# Sheet_1.net
KiCad netlist of a schematic drawn in EasyEDA
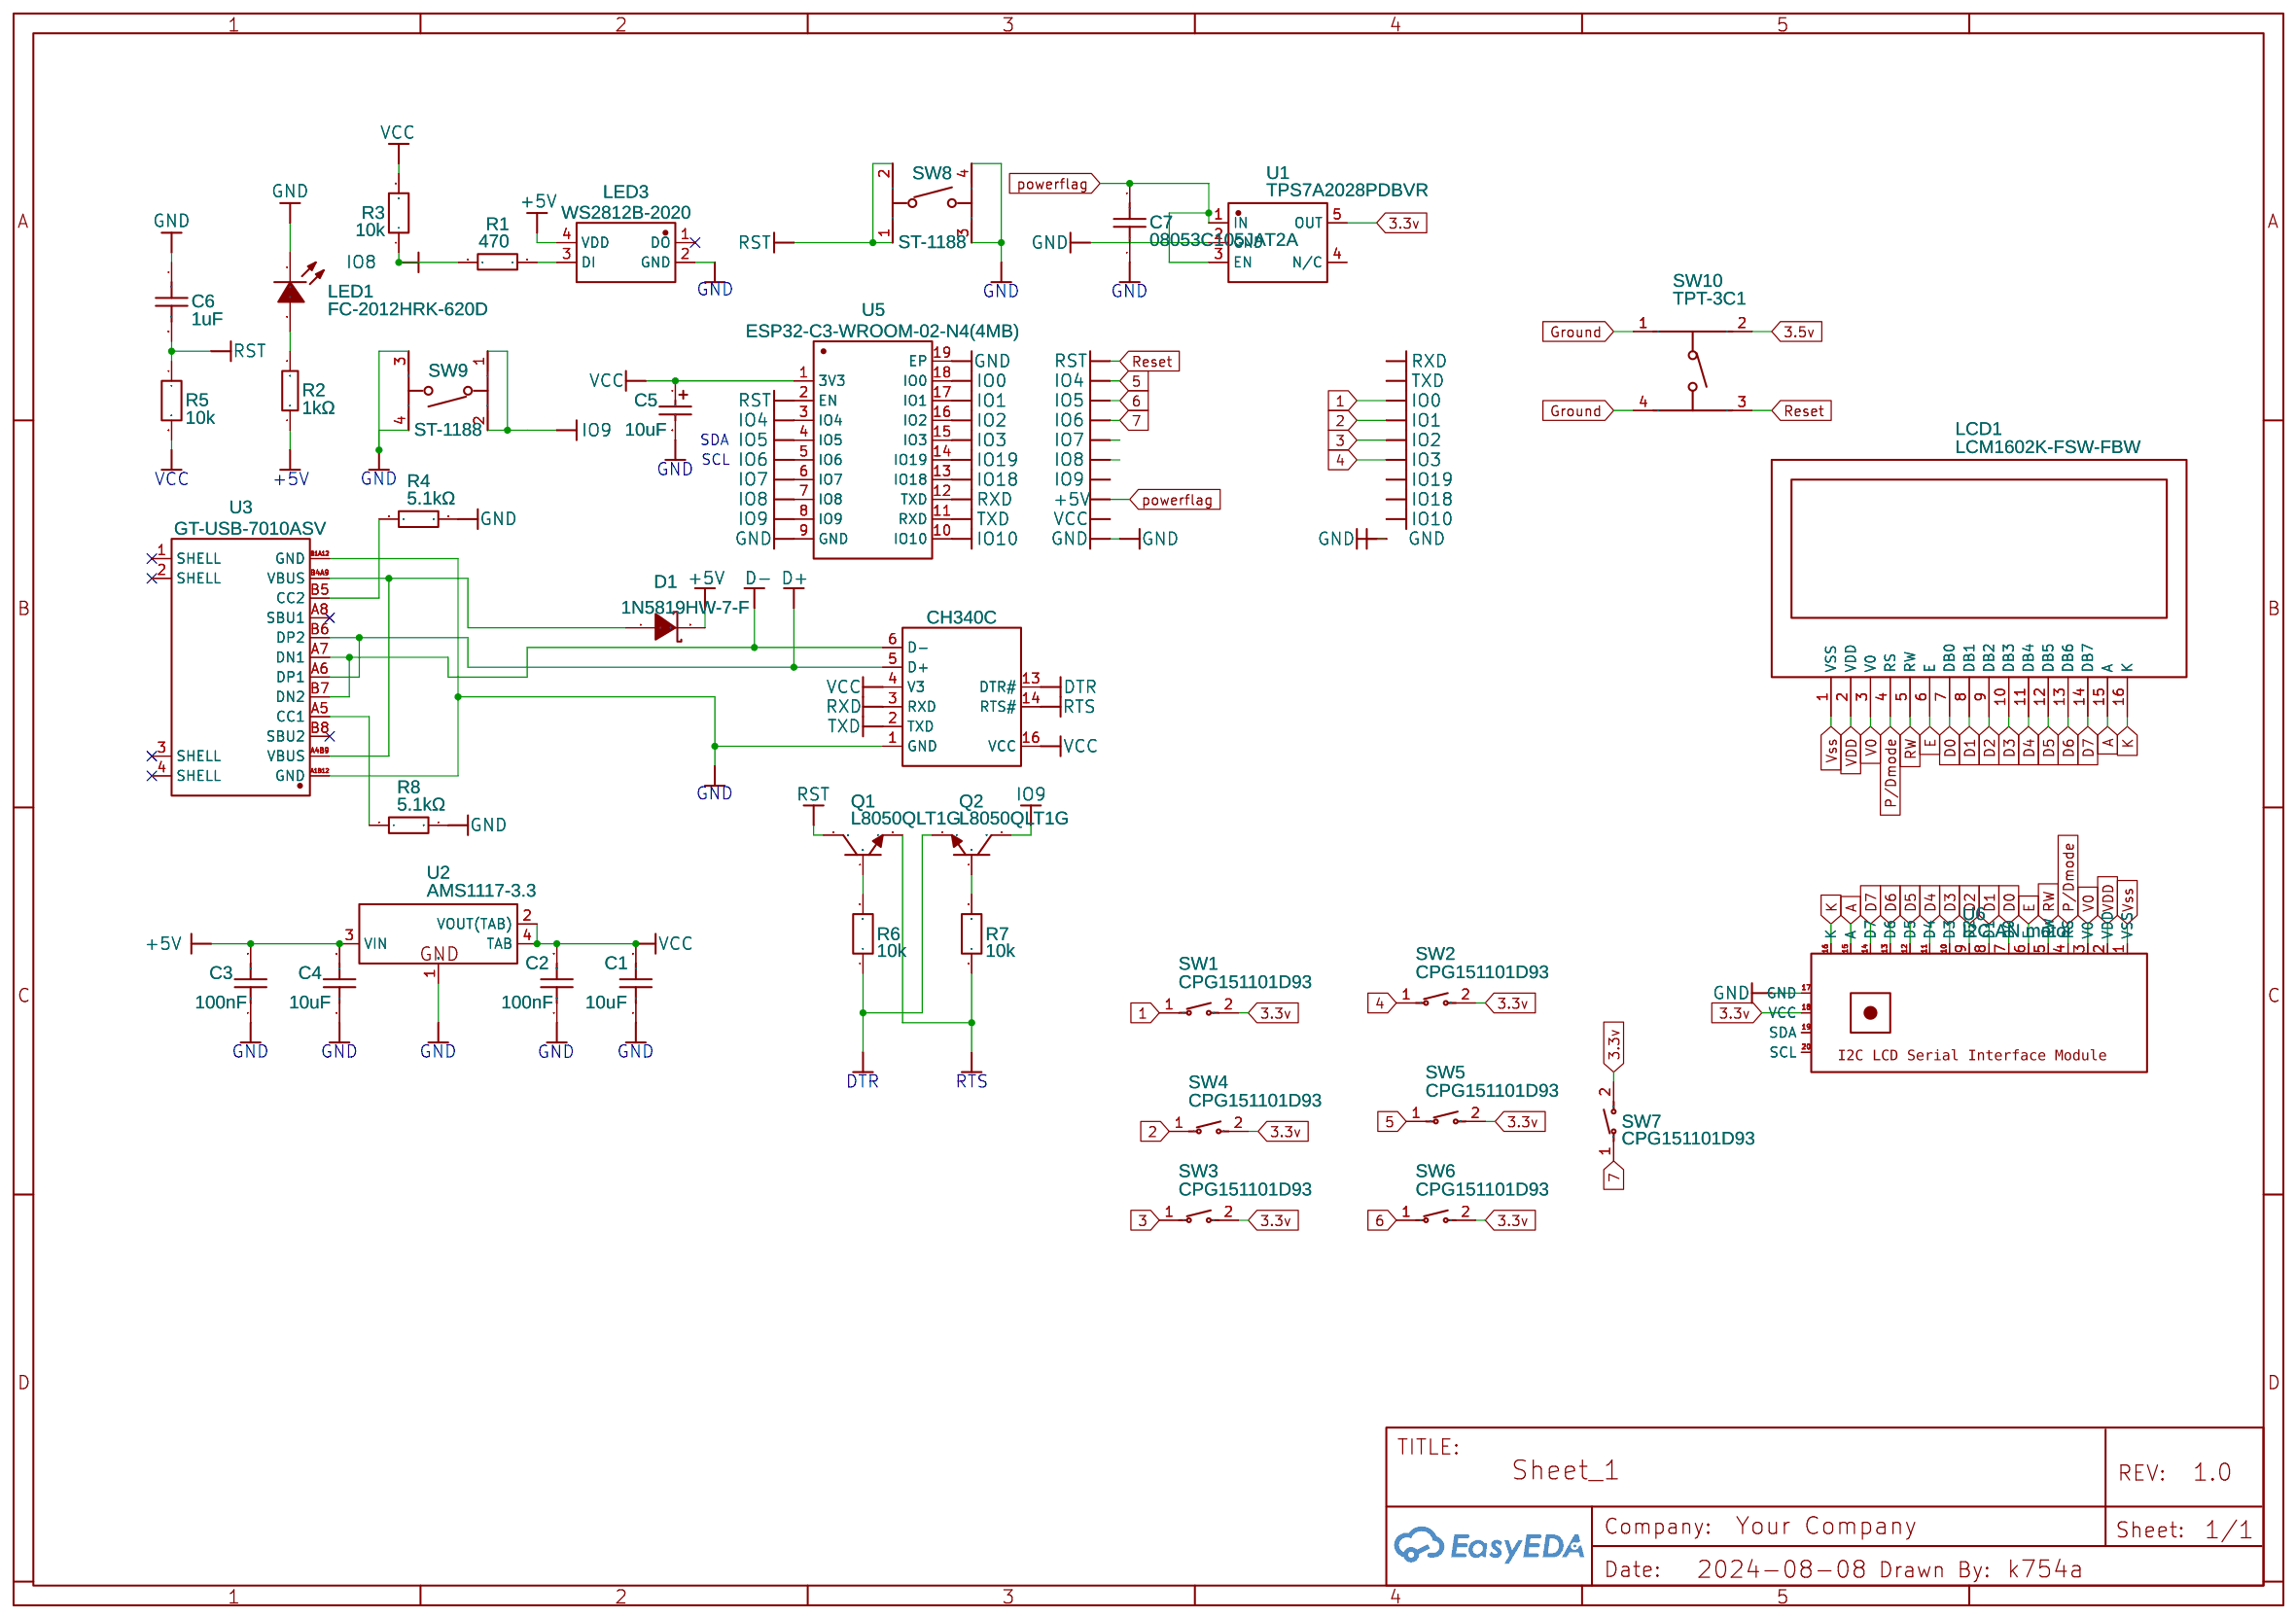
[diagram p0: schematic sheet]

(export (version "E")
  (design (tool "Eeschema 10.0.6"))
  (components
    (comp (ref "C1")
      (value "10uF")
      (fields (field (name "Manufacturer Part") "0805X106M250NT") (field (name "Manufacturer") "FH(风华)"))
      (libsource (lib "") (part "0805X106M250NT"))
    )
    (comp (ref "C2")
      (value "100nF")
      (fields (field (name "Manufacturer Part") "C0603C104J3RACAUTO") (field (name "Manufacturer") "KEMET"))
      (libsource (lib "") (part "C0603C104J3RACAUTO"))
    )
    (comp (ref "C3")
      (value "100nF")
      (fields (field (name "Manufacturer Part") "C0603C104J3RACAUTO") (field (name "Manufacturer") "KEMET"))
      (libsource (lib "") (part "C0603C104J3RACAUTO"))
    )
    (comp (ref "C4")
      (value "10uF")
      (fields (field (name "Manufacturer Part") "0805X106M250NT") (field (name "Manufacturer") "FH(风华)"))
      (libsource (lib "") (part "0805X106M250NT"))
    )
    (comp (ref "C5")
      (value "10uF")
      (fields (field (name "Manufacturer Part") "TAJB106K016RNJ") (field (name "Manufacturer") "Kyocera AVX"))
      (libsource (lib "") (part "TAJB106K016RNJ"))
    )
    (comp (ref "C6")
      (value "1uF")
      (fields (field (name "Manufacturer Part") "CL21B105KBFNNNE") (field (name "Manufacturer") "SAMSUNG"))
      (libsource (lib "") (part "C_0603_US"))
    )
    (comp (ref "C7")
      (value "08053C105JAT2A")
      (fields (field (name "Manufacturer") "KYOCERA AVX"))
      (libsource (lib "") (part "08053C105JAT2A"))
    )
    (comp (ref "D1")
      (value "1N5819HW-7-F")
      (fields (field (name "Manufacturer") "DIODES"))
      (libsource (lib "") (part "1N5819HW-7-F"))
    )
    (comp (ref "LCD1")
      (value "LCM1602K-FSW-FBW")
      (fields (field (name "Manufacturer") "LONTECH(厦门龙特)"))
      (libsource (lib "") (part "LCM1602K-FSW-FBW"))
    )
    (comp (ref "LED1")
      (value "FC-2012HRK-620D")
      (fields (field (name "Manufacturer Part") "NCD0805R1") (field (name "Manufacturer") "国星光电"))
      (libsource (lib "") (part "FC-2012HRK-620D"))
    )
    (comp (ref "LED3")
      (value "WS2812B-2020")
      (fields (field (name "Manufacturer") "worldsemi"))
      (libsource (lib "") (part "WS2812B-2020"))
    )
    (comp (ref "Q1")
      (value "L8050QLT1G")
      (fields (field (name "Manufacturer") "LRC"))
      (libsource (lib "") (part "L8050QLT1G_1"))
    )
    (comp (ref "Q2")
      (value "L8050QLT1G")
      (fields (field (name "Manufacturer") "LRC"))
      (libsource (lib "") (part "L8050QLT1G"))
    )
    (comp (ref "R1")
      (value "470")
      (fields (field (name "Manufacturer Part") "RMC08054701%N") (field (name "Manufacturer") "Tyohm"))
      (libsource (lib "") (part "RMC08054701%N"))
    )
    (comp (ref "R2")
      (value "1kΩ")
      (fields
        (field (name "Manufacturer Part") "0805W8F1001T5E")
        (field (name "Manufacturer") "UNI-ROYAL(厚声)")
      )
      (libsource (lib "") (part "0805W8F1001T5E"))
    )
    (comp (ref "R3")
      (value "10k")
      (fields (field (name "Manufacturer Part") "B57221V2103J060") (field (name "Manufacturer") "TDK"))
      (libsource (lib "") (part "R_0603_EU"))
    )
    (comp (ref "R4")
      (value "5.1kΩ")
      (fields (field (name "Manufacturer Part") "RTT03512JTP") (field (name "Manufacturer") "RALEC(旺诠)"))
      (libsource (lib "") (part "RTT03512JTP"))
    )
    (comp (ref "R5")
      (value "10k")
      (fields (field (name "Manufacturer Part") "B57221V2103J060") (field (name "Manufacturer") "TDK"))
      (libsource (lib "") (part "R_0603_EU_1"))
    )
    (comp (ref "R6")
      (value "10k")
      (fields (field (name "Manufacturer Part") "B57221V2103J060") (field (name "Manufacturer") "TDK"))
      (libsource (lib "") (part "R_0603_EU"))
    )
    (comp (ref "R7")
      (value "10k")
      (fields (field (name "Manufacturer Part") "B57221V2103J060") (field (name "Manufacturer") "TDK"))
      (libsource (lib "") (part "R_0603_EU"))
    )
    (comp (ref "R8")
      (value "5.1kΩ")
      (fields (field (name "Manufacturer Part") "RTT03512JTP") (field (name "Manufacturer") "RALEC(旺诠)"))
      (libsource (lib "") (part "RTT03512JTP"))
    )
    (comp (ref "SW1")
      (value "CPG151101D93")
      (fields (field (name "Manufacturer") "Kailh(凯华)"))
      (libsource (lib "") (part "CPG151101D93"))
    )
    (comp (ref "SW2")
      (value "CPG151101D93")
      (fields (field (name "Manufacturer") "Kailh(凯华)"))
      (libsource (lib "") (part "CPG151101D93"))
    )
    (comp (ref "SW3")
      (value "CPG151101D93")
      (fields (field (name "Manufacturer") "Kailh(凯华)"))
      (libsource (lib "") (part "CPG151101D93"))
    )
    (comp (ref "SW4")
      (value "CPG151101D93")
      (fields (field (name "Manufacturer") "Kailh(凯华)"))
      (libsource (lib "") (part "CPG151101D93"))
    )
    (comp (ref "SW5")
      (value "CPG151101D93")
      (fields (field (name "Manufacturer") "Kailh(凯华)"))
      (libsource (lib "") (part "CPG151101D93"))
    )
    (comp (ref "SW6")
      (value "CPG151101D93")
      (fields (field (name "Manufacturer") "Kailh(凯华)"))
      (libsource (lib "") (part "CPG151101D93"))
    )
    (comp (ref "SW7")
      (value "CPG151101D93")
      (fields (field (name "Manufacturer") "Kailh(凯华)"))
      (libsource (lib "") (part "CPG151101D93_1"))
    )
    (comp (ref "SW8")
      (value "ST-1188")
      (fields (field (name "Manufacturer") "RI SHENG"))
      (libsource (lib "") (part "ST-1188_1"))
    )
    (comp (ref "SW9")
      (value "ST-1188")
      (fields (field (name "Manufacturer") "RI SHENG"))
      (libsource (lib "") (part "ST-1188"))
    )
    (comp (ref "SW10")
      (value "TPT-3C1")
      (fields (field (name "Manufacturer") "ROCPU Switches(台普)"))
      (libsource (lib "") (part "TPT-3C1"))
    )
    (comp (ref "U1")
      (value "TPS7A2028PDBVR")
      (fields (field (name "Manufacturer") "TI(德州仪器)"))
      (libsource (lib "") (part "TPS7A2028PDBVR"))
    )
    (comp (ref "U2")
      (value "AMS1117-3.3")
      (fields (field (name "Manufacturer") "Youtai Semiconductor Co., Ltd."))
      (libsource (lib "") (part "AMS1117-3.3"))
    )
    (comp (ref "U3")
      (value "GT-USB-7010ASV")
      (fields (field (name "Manufacturer") "G-Switch(品赞)"))
      (libsource (lib "") (part "GT-USB-7010ASV"))
    )
    (comp (ref "U4")
      (value "CH340C")
      (fields (field (name "Manufacturer") "WCH"))
      (libsource (lib "") (part "CH340C"))
    )
    (comp (ref "U5")
      (value "ESP32-C3-WROOM-02-N4(4MB)")
      (fields (field (name "Manufacturer") "ESPRESSIF 乐鑫"))
      (libsource (lib "") (part "ESP32-C3-WROOM-02-N4(4MB)"))
    )
    (comp (ref "U6") (value "I2C AN motor") (libsource (lib "") (part "I2C AN motor")))
  )
  (nets
    (net (code "1") (name "1") (class "Default")
      (node (ref "SW1") (pin "1") (pinfunction "1_1") (pintype "unspecified"))
      (node (ref "U5") (pin "18") (pinfunction "IO0_18") (pintype "unspecified"))
    )
    (net (code "2") (name "2") (class "Default")
      (node (ref "SW4") (pin "1") (pinfunction "1_1") (pintype "unspecified"))
      (node (ref "U5") (pin "17") (pinfunction "IO1_17") (pintype "unspecified"))
    )
    (net (code "3") (name "3") (class "Default")
      (node (ref "SW3") (pin "1") (pinfunction "1_1") (pintype "unspecified"))
      (node (ref "U5") (pin "16") (pinfunction "IO2_16") (pintype "unspecified"))
    )
    (net (code "4") (name "3.3v") (class "Default")
      (node (ref "SW1") (pin "2") (pinfunction "2_2") (pintype "unspecified"))
      (node (ref "SW2") (pin "2") (pinfunction "2_2") (pintype "unspecified"))
      (node (ref "SW3") (pin "2") (pinfunction "2_2") (pintype "unspecified"))
      (node (ref "SW4") (pin "2") (pinfunction "2_2") (pintype "unspecified"))
      (node (ref "SW5") (pin "2") (pinfunction "2_2") (pintype "unspecified"))
      (node (ref "SW6") (pin "2") (pinfunction "2_2") (pintype "unspecified"))
      (node (ref "SW7") (pin "2") (pinfunction "2_2") (pintype "unspecified"))
      (node (ref "U1") (pin "5") (pinfunction "OUT_5") (pintype "unspecified"))
    )
    (net (code "5") (name "3.5v") (class "Default")
      (node (ref "SW10") (pin "2") (pinfunction "2_2") (pintype "unspecified"))
    )
    (net (code "6") (name "4") (class "Default")
      (node (ref "SW2") (pin "1") (pinfunction "1_1") (pintype "unspecified"))
      (node (ref "U5") (pin "15") (pinfunction "IO3_15") (pintype "unspecified"))
    )
    (net (code "7") (name "5") (class "Default")
      (node (ref "SW5") (pin "1") (pinfunction "1_1") (pintype "unspecified"))
      (node (ref "U5") (pin "3") (pinfunction "IO4_3") (pintype "unspecified"))
    )
    (net (code "8") (name "6") (class "Default")
      (node (ref "SW6") (pin "1") (pinfunction "1_1") (pintype "unspecified"))
      (node (ref "U5") (pin "4") (pinfunction "IO5_4") (pintype "unspecified"))
    )
    (net (code "9") (name "7") (class "Default")
      (node (ref "SW7") (pin "1") (pinfunction "1_1") (pintype "unspecified"))
      (node (ref "U5") (pin "5") (pinfunction "IO6_5") (pintype "unspecified"))
    )
    (net (code "10") (name "A") (class "Default")
      (node (ref "LCD1") (pin "15") (pinfunction "A_15") (pintype "unspecified"))
    )
    (net (code "11") (name "D+") (class "Default")
      (node (ref "U3") (pin "A6") (pinfunction "DP1_A6") (pintype "unspecified"))
      (node (ref "U3") (pin "B6") (pinfunction "DP2_B6") (pintype "unspecified"))
      (node (ref "U4") (pin "5") (pinfunction "D+_5") (pintype "unspecified"))
    )
    (net (code "12") (name "D-") (class "Default")
      (node (ref "U3") (pin "A7") (pinfunction "DN1_A7") (pintype "unspecified"))
      (node (ref "U3") (pin "B7") (pinfunction "DN2_B7") (pintype "unspecified"))
      (node (ref "U4") (pin "6") (pinfunction "D-_6") (pintype "unspecified"))
    )
    (net (code "13") (name "D0") (class "Default")
      (node (ref "LCD1") (pin "7") (pinfunction "DB0_7") (pintype "unspecified"))
    )
    (net (code "14") (name "D1") (class "Default")
      (node (ref "LCD1") (pin "8") (pinfunction "DB1_8") (pintype "unspecified"))
    )
    (net (code "15") (name "D2") (class "Default")
      (node (ref "LCD1") (pin "9") (pinfunction "DB2_9") (pintype "unspecified"))
    )
    (net (code "16") (name "D3") (class "Default")
      (node (ref "LCD1") (pin "10") (pinfunction "DB3_10") (pintype "unspecified"))
    )
    (net (code "17") (name "D4") (class "Default")
      (node (ref "LCD1") (pin "11") (pinfunction "DB4_11") (pintype "unspecified"))
    )
    (net (code "18") (name "D5") (class "Default")
      (node (ref "LCD1") (pin "12") (pinfunction "DB5_12") (pintype "unspecified"))
    )
    (net (code "19") (name "D6") (class "Default")
      (node (ref "LCD1") (pin "13") (pinfunction "DB6_13") (pintype "unspecified"))
    )
    (net (code "20") (name "D7") (class "Default")
      (node (ref "LCD1") (pin "14") (pinfunction "DB7_14") (pintype "unspecified"))
    )
    (net (code "21") (name "DTR") (class "Default")
      (node (ref "Q2") (pin "2") (pinfunction "E_2") (pintype "unspecified"))
      (node (ref "R6") (pin "1") (pinfunction "1_1") (pintype "unspecified"))
      (node (ref "U4") (pin "13") (pinfunction "DTR#_13") (pintype "unspecified"))
    )
    (net (code "22") (name "E") (class "Default")
      (node (ref "LCD1") (pin "6") (pinfunction "E_6") (pintype "unspecified"))
    )
    (net (code "23") (name "GND") (class "Default")
      (node (ref "C1") (pin "1") (pinfunction "1_1") (pintype "unspecified"))
      (node (ref "C2") (pin "1") (pinfunction "1_1") (pintype "unspecified"))
      (node (ref "C3") (pin "1") (pinfunction "1_1") (pintype "unspecified"))
      (node (ref "C4") (pin "1") (pinfunction "1_1") (pintype "unspecified"))
      (node (ref "C5") (pin "2") (pinfunction "2_2") (pintype "input"))
      (node (ref "C6") (pin "1") (pinfunction "1_1") (pintype "unspecified"))
      (node (ref "C7") (pin "1") (pinfunction "1_1") (pintype "unspecified"))
      (node (ref "LED1") (pin "1") (pinfunction "-_1") (pintype "unspecified"))
      (node (ref "LED3") (pin "2") (pinfunction "GND_2") (pintype "unspecified"))
      (node (ref "R4") (pin "2") (pinfunction "2_2") (pintype "input"))
      (node (ref "R8") (pin "2") (pinfunction "2_2") (pintype "input"))
      (node (ref "SW8") (pin "3") (pinfunction "3_3") (pintype "unspecified"))
      (node (ref "SW8") (pin "4") (pinfunction "4_4") (pintype "unspecified"))
      (node (ref "SW9") (pin "3") (pinfunction "3_3") (pintype "unspecified"))
      (node (ref "SW9") (pin "4") (pinfunction "4_4") (pintype "unspecified"))
      (node (ref "U1") (pin "2") (pinfunction "GND_2") (pintype "unspecified"))
      (node (ref "U2") (pin "1") (pinfunction "ADJ(GND)_1") (pintype "unspecified"))
      (node (ref "U3") (pin "A1B12") (pinfunction "GND_A1B12") (pintype "unspecified"))
      (node (ref "U3") (pin "B1A12") (pinfunction "GND_B1A12") (pintype "unspecified"))
      (node (ref "U4") (pin "1") (pinfunction "GND_1") (pintype "unspecified"))
      (node (ref "U5") (pin "19") (pinfunction "EP_19") (pintype "unspecified"))
      (node (ref "U5") (pin "9") (pinfunction "GND_9") (pintype "unspecified"))
    )
    (net (code "24") (name "Ground") (class "Default")
      (node (ref "SW10") (pin "1") (pinfunction "1_1") (pintype "unspecified"))
      (node (ref "SW10") (pin "4") (pinfunction "4_4") (pintype "unspecified"))
    )
    (net (code "25") (name "IO7") (class "Default")
      (node (ref "U5") (pin "6") (pinfunction "IO7_6") (pintype "unspecified"))
    )
    (net (code "26") (name "IO8") (class "Default")
      (node (ref "R1") (pin "2") (pinfunction "2_2") (pintype "unspecified"))
      (node (ref "R3") (pin "1") (pinfunction "1_1") (pintype "unspecified"))
      (node (ref "U5") (pin "7") (pinfunction "IO8_7") (pintype "unspecified"))
    )
    (net (code "27") (name "IO9") (class "Default")
      (node (ref "Q2") (pin "3") (pinfunction "C_3") (pintype "unspecified"))
      (node (ref "SW9") (pin "1") (pinfunction "1_1") (pintype "unspecified"))
      (node (ref "SW9") (pin "2") (pinfunction "2_2") (pintype "unspecified"))
      (node (ref "U5") (pin "8") (pinfunction "IO9_8") (pintype "unspecified"))
    )
    (net (code "28") (name "IO10") (class "Default")
      (node (ref "U5") (pin "10") (pinfunction "IO10_10") (pintype "unspecified"))
    )
    (net (code "29") (name "IO18") (class "Default")
      (node (ref "U5") (pin "13") (pinfunction "IO18_13") (pintype "unspecified"))
    )
    (net (code "30") (name "IO19") (class "Default")
      (node (ref "U5") (pin "14") (pinfunction "IO19_14") (pintype "unspecified"))
    )
    (net (code "31") (name "K") (class "Default")
      (node (ref "LCD1") (pin "16") (pinfunction "K_16") (pintype "unspecified"))
    )
    (net (code "32") (name "Net-(D1-A)") (class "Default")
      (node (ref "D1") (pin "1") (pinfunction "A_1") (pintype "unspecified"))
      (node (ref "U3") (pin "A4B9") (pinfunction "VBUS_A4B9") (pintype "unspecified"))
      (node (ref "U3") (pin "B4A9") (pinfunction "VBUS_B4A9") (pintype "unspecified"))
    )
    (net (code "33") (name "Net-(LED1-+)") (class "Default")
      (node (ref "LED1") (pin "2") (pinfunction "+_2") (pintype "unspecified"))
      (node (ref "R2") (pin "2") (pinfunction "2_2") (pintype "input"))
    )
    (net (code "34") (name "Net-(LED3-DI)") (class "Default")
      (node (ref "LED3") (pin "3") (pinfunction "DI_3") (pintype "unspecified"))
      (node (ref "R1") (pin "1") (pinfunction "1_1") (pintype "unspecified"))
    )
    (net (code "35") (name "Net-(Q1-B)") (class "Default")
      (node (ref "Q1") (pin "1") (pinfunction "B_1") (pintype "unspecified"))
      (node (ref "R6") (pin "2") (pinfunction "2_2") (pintype "unspecified"))
    )
    (net (code "36") (name "Net-(Q2-B)") (class "Default")
      (node (ref "Q2") (pin "1") (pinfunction "B_1") (pintype "unspecified"))
      (node (ref "R7") (pin "2") (pinfunction "2_2") (pintype "unspecified"))
    )
    (net (code "37") (name "Net-(U3-CC1)") (class "Default")
      (node (ref "R8") (pin "1") (pinfunction "1_1") (pintype "input"))
      (node (ref "U3") (pin "A5") (pinfunction "CC1_A5") (pintype "unspecified"))
    )
    (net (code "38") (name "Net-(U3-CC2)") (class "Default")
      (node (ref "R4") (pin "1") (pinfunction "1_1") (pintype "input"))
      (node (ref "U3") (pin "B5") (pinfunction "CC2_B5") (pintype "unspecified"))
    )
    (net (code "39") (name "P{slash}Dmode") (class "Default")
      (node (ref "LCD1") (pin "4") (pinfunction "RS_4") (pintype "unspecified"))
    )
    (net (code "40") (name "RTS") (class "Default")
      (node (ref "Q1") (pin "2") (pinfunction "E_2") (pintype "unspecified"))
      (node (ref "R7") (pin "1") (pinfunction "1_1") (pintype "unspecified"))
      (node (ref "U4") (pin "14") (pinfunction "RTS#_14") (pintype "unspecified"))
    )
    (net (code "41") (name "RW") (class "Default")
      (node (ref "LCD1") (pin "5") (pinfunction "RW_5") (pintype "unspecified"))
    )
    (net (code "42") (name "RXD") (class "Default")
      (node (ref "U4") (pin "3") (pinfunction "RXD_3") (pintype "unspecified"))
      (node (ref "U5") (pin "12") (pinfunction "TXD_12") (pintype "unspecified"))
    )
    (net (code "43") (name "Reset") (class "Default")
      (node (ref "C6") (pin "2") (pinfunction "2_2") (pintype "unspecified"))
      (node (ref "Q1") (pin "3") (pinfunction "C_3") (pintype "unspecified"))
      (node (ref "R5") (pin "1") (pinfunction "1_1") (pintype "unspecified"))
      (node (ref "SW10") (pin "3") (pinfunction "3_3") (pintype "unspecified"))
      (node (ref "SW8") (pin "1") (pinfunction "1_1") (pintype "unspecified"))
      (node (ref "SW8") (pin "2") (pinfunction "2_2") (pintype "unspecified"))
      (node (ref "U5") (pin "2") (pinfunction "EN_2") (pintype "unspecified"))
    )
    (net (code "44") (name "TXD") (class "Default")
      (node (ref "U4") (pin "2") (pinfunction "TXD_2") (pintype "unspecified"))
      (node (ref "U5") (pin "11") (pinfunction "RXD_11") (pintype "unspecified"))
    )
    (net (code "45") (name "V0") (class "Default")
      (node (ref "LCD1") (pin "3") (pinfunction "V0_3") (pintype "unspecified"))
    )
    (net (code "46") (name "VCC") (class "Default")
      (node (ref "C1") (pin "2") (pinfunction "2_2") (pintype "unspecified"))
      (node (ref "C2") (pin "2") (pinfunction "2_2") (pintype "unspecified"))
      (node (ref "C5") (pin "1") (pinfunction "1_1") (pintype "input"))
      (node (ref "R3") (pin "2") (pinfunction "2_2") (pintype "unspecified"))
      (node (ref "R5") (pin "2") (pinfunction "2_2") (pintype "unspecified"))
      (node (ref "U2") (pin "2") (pinfunction "VOUT(TAB)_2") (pintype "unspecified"))
      (node (ref "U2") (pin "4") (pinfunction "TAB_4") (pintype "unspecified"))
      (node (ref "U4") (pin "16") (pinfunction "VCC_16") (pintype "unspecified"))
      (node (ref "U4") (pin "4") (pinfunction "V3_4") (pintype "unspecified"))
      (node (ref "U5") (pin "1") (pinfunction "3V3_1") (pintype "unspecified"))
    )
    (net (code "47") (name "VDD") (class "Default")
      (node (ref "LCD1") (pin "2") (pinfunction "VDD_2") (pintype "unspecified"))
    )
    (net (code "48") (name "Vss") (class "Default")
      (node (ref "LCD1") (pin "1") (pinfunction "VSS_1") (pintype "unspecified"))
    )
    (net (code "49") (name "powerflag") (class "Default")
      (node (ref "C3") (pin "2") (pinfunction "2_2") (pintype "unspecified"))
      (node (ref "C4") (pin "2") (pinfunction "2_2") (pintype "unspecified"))
      (node (ref "C7") (pin "2") (pinfunction "2_2") (pintype "unspecified"))
      (node (ref "D1") (pin "2") (pinfunction "K_2") (pintype "unspecified"))
      (node (ref "LED3") (pin "4") (pinfunction "VDD_4") (pintype "unspecified"))
      (node (ref "R2") (pin "1") (pinfunction "1_1") (pintype "input"))
      (node (ref "U1") (pin "1") (pinfunction "IN_1") (pintype "unspecified"))
      (node (ref "U1") (pin "3") (pinfunction "EN_3") (pintype "unspecified"))
      (node (ref "U2") (pin "3") (pinfunction "VIN_3") (pintype "unspecified"))
    )
    (net (code "50") (name "unconnected-(LED3-DO-Pad1)") (class "Default")
      (node (ref "LED3") (pin "1") (pinfunction "DO_1") (pintype "unspecified+no_connect"))
    )
    (net (code "51") (name "unconnected-(U1-N{slash}C-Pad4)") (class "Default")
      (node (ref "U1") (pin "4") (pinfunction "N/C_4") (pintype "unspecified"))
    )
    (net (code "52") (name "unconnected-(U3-SBU1-PadA8)") (class "Default")
      (node (ref "U3") (pin "A8") (pinfunction "SBU1_A8") (pintype "unspecified+no_connect"))
    )
    (net (code "53") (name "unconnected-(U3-SBU2-PadB8)") (class "Default")
      (node (ref "U3") (pin "B8") (pinfunction "SBU2_B8") (pintype "unspecified+no_connect"))
    )
    (net (code "54") (name "unconnected-(U3-SHELL-Pad1)") (class "Default")
      (node (ref "U3") (pin "1") (pinfunction "SHELL_1") (pintype "unspecified+no_connect"))
    )
    (net (code "55") (name "unconnected-(U3-SHELL-Pad2)") (class "Default")
      (node (ref "U3") (pin "2") (pinfunction "SHELL_2") (pintype "unspecified+no_connect"))
    )
    (net (code "56") (name "unconnected-(U3-SHELL-Pad3)") (class "Default")
      (node (ref "U3") (pin "3") (pinfunction "SHELL_3") (pintype "unspecified+no_connect"))
    )
    (net (code "57") (name "unconnected-(U3-SHELL-Pad4)") (class "Default")
      (node (ref "U3") (pin "4") (pinfunction "SHELL_4") (pintype "unspecified+no_connect"))
    )
    (net (code "58") (name "unconnected-(U6-A-Pad15)") (class "Default")
      (node (ref "U6") (pin "15") (pinfunction "A_15") (pintype "unspecified"))
    )
    (net (code "59") (name "unconnected-(U6-D0-Pad7)") (class "Default")
      (node (ref "U6") (pin "7") (pinfunction "D0_7") (pintype "unspecified"))
    )
    (net (code "60") (name "unconnected-(U6-D1-Pad8)") (class "Default")
      (node (ref "U6") (pin "8") (pinfunction "D1_8") (pintype "unspecified"))
    )
    (net (code "61") (name "unconnected-(U6-D2-Pad9)") (class "Default")
      (node (ref "U6") (pin "9") (pinfunction "D2_9") (pintype "unspecified"))
    )
    (net (code "62") (name "unconnected-(U6-D3-Pad10)") (class "Default")
      (node (ref "U6") (pin "10") (pinfunction "D3_10") (pintype "unspecified"))
    )
    (net (code "63") (name "unconnected-(U6-D4-Pad11)") (class "Default")
      (node (ref "U6") (pin "11") (pinfunction "D4_11") (pintype "unspecified"))
    )
    (net (code "64") (name "unconnected-(U6-D5-Pad12)") (class "Default")
      (node (ref "U6") (pin "12") (pinfunction "D5_12") (pintype "unspecified"))
    )
    (net (code "65") (name "unconnected-(U6-D6-Pad13)") (class "Default")
      (node (ref "U6") (pin "13") (pinfunction "D6_13") (pintype "unspecified"))
    )
    (net (code "66") (name "unconnected-(U6-D7-Pad14)") (class "Default")
      (node (ref "U6") (pin "14") (pinfunction "D7_14") (pintype "unspecified"))
    )
    (net (code "67") (name "unconnected-(U6-E-Pad6)") (class "Default")
      (node (ref "U6") (pin "6") (pinfunction "E_6") (pintype "unspecified"))
    )
    (net (code "68") (name "unconnected-(U6-GND-Pad17)") (class "Default")
      (node (ref "U6") (pin "17") (pinfunction "GND_17") (pintype "unspecified"))
    )
    (net (code "69") (name "unconnected-(U6-K-Pad16)") (class "Default")
      (node (ref "U6") (pin "16") (pinfunction "K_16") (pintype "unspecified"))
    )
    (net (code "70") (name "unconnected-(U6-RS-Pad4)") (class "Default")
      (node (ref "U6") (pin "4") (pinfunction "RS_4") (pintype "unspecified"))
    )
    (net (code "71") (name "unconnected-(U6-RW-Pad5)") (class "Default")
      (node (ref "U6") (pin "5") (pinfunction "RW_5") (pintype "unspecified"))
    )
    (net (code "72") (name "unconnected-(U6-SCL-Pad20)") (class "Default")
      (node (ref "U6") (pin "20") (pinfunction "SCL_20") (pintype "unspecified"))
    )
    (net (code "73") (name "unconnected-(U6-SDA-Pad19)") (class "Default")
      (node (ref "U6") (pin "19") (pinfunction "SDA_19") (pintype "unspecified"))
    )
    (net (code "74") (name "unconnected-(U6-V0-Pad3)") (class "Default")
      (node (ref "U6") (pin "3") (pinfunction "V0_3") (pintype "unspecified"))
    )
    (net (code "75") (name "unconnected-(U6-VCC-Pad18)") (class "Default")
      (node (ref "U6") (pin "18") (pinfunction "VCC_18") (pintype "unspecified"))
    )
    (net (code "76") (name "unconnected-(U6-VDD-Pad2)") (class "Default")
      (node (ref "U6") (pin "2") (pinfunction "VDD_2") (pintype "unspecified"))
    )
    (net (code "77") (name "unconnected-(U6-VSS-Pad1)") (class "Default")
      (node (ref "U6") (pin "1") (pinfunction "VSS_1") (pintype "unspecified"))
    )
  )
)
